# Thetis_RevF3_SCH.net
KiCad netlist of a schematic drawn in EAGLE
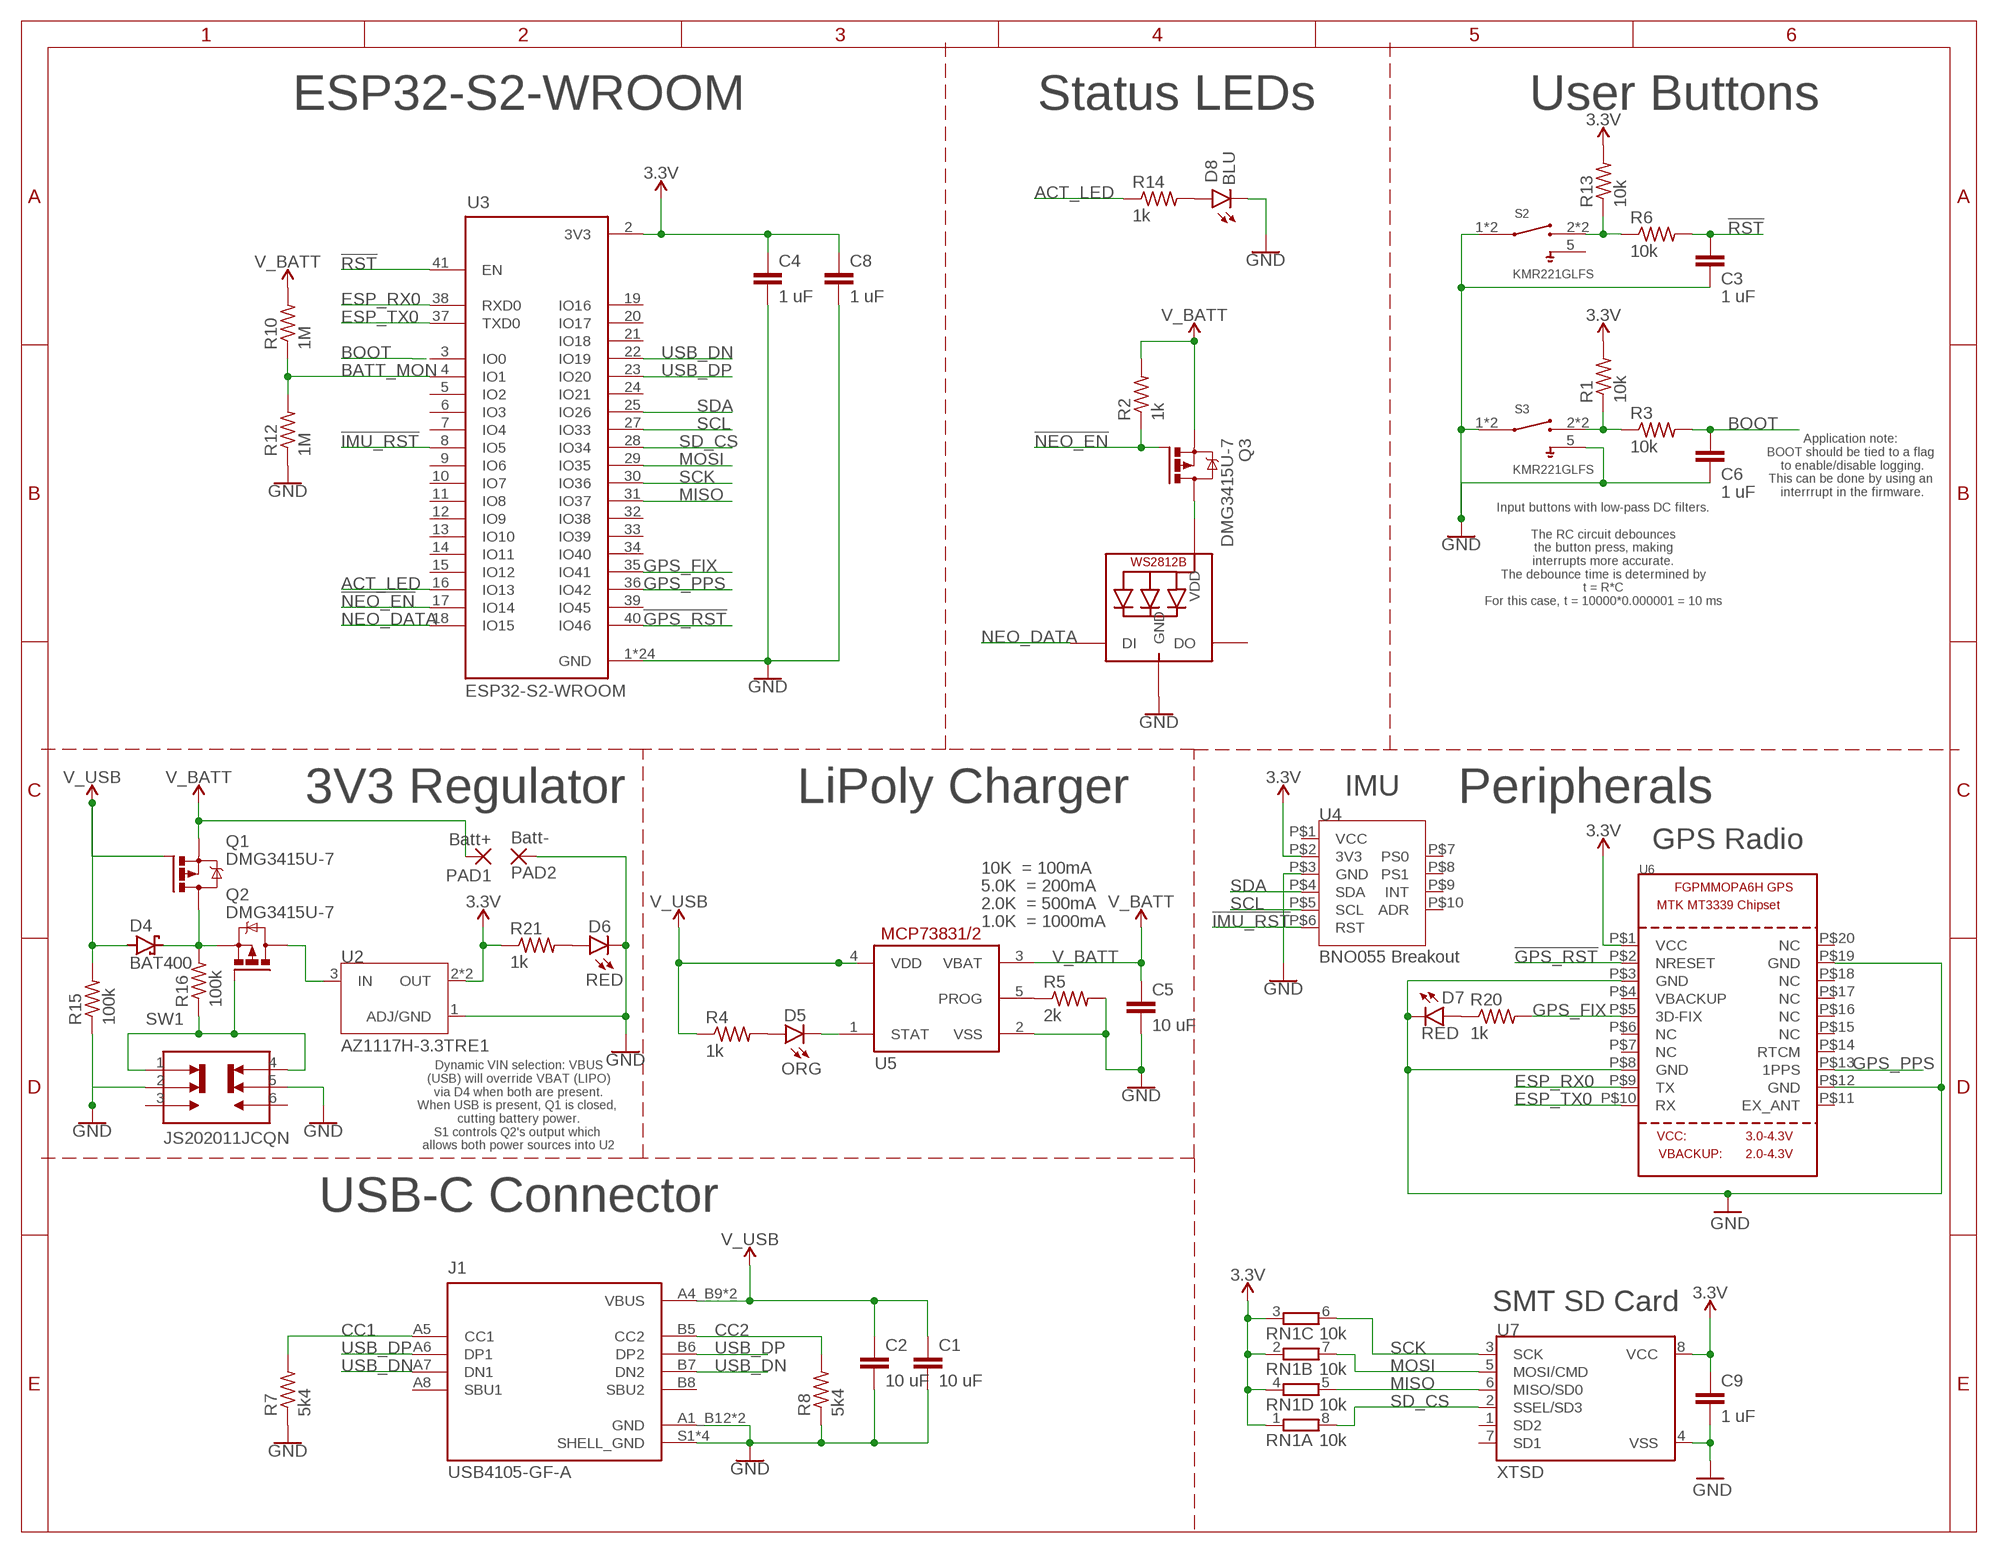
[diagram p0: schematic, sheet 1]

(export (version "E")
  (design (tool "Eeschema 10.0.6"))
  (components
    (comp (ref "C1")
      (value "10 uF")
      (footprint "eagle-import:C0603")
      (libsource (lib "eagle-import") (part "C-EUC0603"))
    )
    (comp (ref "C2")
      (value "10 uF")
      (footprint "eagle-import:C0603")
      (libsource (lib "eagle-import") (part "C-EUC0603"))
    )
    (comp (ref "C3")
      (value "1 uF")
      (footprint "eagle-import:C0603")
      (libsource (lib "eagle-import") (part "C-EUC0603"))
    )
    (comp (ref "C4")
      (value "1 uF")
      (footprint "eagle-import:C0603")
      (libsource (lib "eagle-import") (part "C-EUC0603"))
    )
    (comp (ref "C5")
      (value "10 uF")
      (footprint "eagle-import:C0603")
      (libsource (lib "eagle-import") (part "C-EUC0603"))
    )
    (comp (ref "C6")
      (value "1 uF")
      (footprint "eagle-import:C0603")
      (libsource (lib "eagle-import") (part "C-EUC0603"))
    )
    (comp (ref "C8")
      (value "1 uF")
      (footprint "eagle-import:C0603")
      (libsource (lib "eagle-import") (part "C-EUC0603"))
    )
    (comp (ref "C9")
      (value "1 uF")
      (footprint "eagle-import:C0603")
      (libsource (lib "eagle-import") (part "C-EUC0603"))
    )
    (comp (ref "D4")
      (value "BAT400")
      (footprint "eagle-import:SOT23")
      (libsource (lib "eagle-import") (part "BAS40"))
    )
    (comp (ref "D5")
      (value "ORG")
      (footprint "eagle-import:LEDC1608X65N")
      (libsource (lib "eagle-import") (part "CHIP-ROUND-G_0603"))
    )
    (comp (ref "D6")
      (value "RED")
      (footprint "eagle-import:LEDC1608X65N")
      (libsource (lib "eagle-import") (part "CHIP-ROUND-G_0603"))
    )
    (comp (ref "D7")
      (value "RED")
      (footprint "eagle-import:LEDC1608X35N")
      (libsource (lib "eagle-import") (part "CHIP-FLAT-Y_0603-0.35MM"))
    )
    (comp (ref "D8")
      (value "BLU")
      (footprint "eagle-import:LEDC1608X65N")
      (libsource (lib "eagle-import") (part "CHIP-ROUND-G_0603"))
    )
    (comp (ref "J1")
      (value "USB4105-GF-A")
      (footprint "eagle-import:GCT_USB4105-GF-A")
      (fields (field (name "MF") "GCT"))
      (libsource (lib "eagle-import") (part "USB4105-GF-A"))
    )
    (comp (ref "LED1")
      (value "WS2812B3535")
      (footprint "eagle-import:LED3535")
      (libsource (lib "eagle-import") (part "WS2812B3535"))
    )
    (comp (ref "PAD1")
      (value "Batt+")
      (footprint "eagle-import:SMD2,54-5,08")
      (libsource (lib "eagle-import") (part "SMD5"))
    )
    (comp (ref "PAD2")
      (value "Batt-")
      (footprint "eagle-import:SMD2,54-5,08")
      (libsource (lib "eagle-import") (part "SMD5"))
    )
    (comp (ref "Q1")
      (value "DMG3415U-7")
      (footprint "eagle-import:SOT23")
      (fields (field (name "MANUFACTURER") "ON Semiconductor") (field (name "MPN") "BSS84"))
      (libsource (lib "eagle-import") (part "PMOSFET_BSS84"))
    )
    (comp (ref "Q2")
      (value "DMG3415U-7")
      (footprint "eagle-import:SOT23")
      (fields (field (name "MANUFACTURER") "ON Semiconductor") (field (name "MPN") "BSS84"))
      (libsource (lib "eagle-import") (part "PMOSFET_BSS84"))
    )
    (comp (ref "Q3")
      (value "DMG3415U-7")
      (footprint "eagle-import:SOT23")
      (fields (field (name "MANUFACTURER") "ON Semiconductor") (field (name "MPN") "BSS84"))
      (libsource (lib "eagle-import") (part "PMOSFET_BSS84"))
    )
    (comp (ref "R1")
      (value "10k")
      (footprint "eagle-import:R0603")
      (libsource (lib "eagle-import") (part "R-US_R0603"))
    )
    (comp (ref "R2")
      (value "1k")
      (footprint "eagle-import:R0603")
      (libsource (lib "eagle-import") (part "R-US_R0603"))
    )
    (comp (ref "R3")
      (value "10k")
      (footprint "eagle-import:R0603")
      (libsource (lib "eagle-import") (part "R-US_R0603"))
    )
    (comp (ref "R4")
      (value "1k")
      (footprint "eagle-import:R0603")
      (libsource (lib "eagle-import") (part "R-US_R0603"))
    )
    (comp (ref "R5")
      (value "2k")
      (footprint "eagle-import:R0603")
      (libsource (lib "eagle-import") (part "R-US_R0603"))
    )
    (comp (ref "R6")
      (value "10k")
      (footprint "eagle-import:R0603")
      (libsource (lib "eagle-import") (part "R-US_R0603"))
    )
    (comp (ref "R7")
      (value "5k4")
      (footprint "eagle-import:R0603")
      (libsource (lib "eagle-import") (part "R-US_R0603"))
    )
    (comp (ref "R8")
      (value "5k4")
      (footprint "eagle-import:R0603")
      (libsource (lib "eagle-import") (part "R-US_R0603"))
    )
    (comp (ref "R10")
      (value "1M")
      (footprint "eagle-import:R0603")
      (libsource (lib "eagle-import") (part "R-US_R0603"))
    )
    (comp (ref "R12")
      (value "1M")
      (footprint "eagle-import:R0603")
      (libsource (lib "eagle-import") (part "R-US_R0603"))
    )
    (comp (ref "R13")
      (value "10k")
      (footprint "eagle-import:R0603")
      (libsource (lib "eagle-import") (part "R-US_R0603"))
    )
    (comp (ref "R14")
      (value "1k")
      (footprint "eagle-import:R0603")
      (libsource (lib "eagle-import") (part "R-US_R0603"))
    )
    (comp (ref "R15")
      (value "100k")
      (footprint "eagle-import:R0603")
      (libsource (lib "eagle-import") (part "R-US_R0603"))
    )
    (comp (ref "R16")
      (value "100k")
      (footprint "eagle-import:R0603")
      (libsource (lib "eagle-import") (part "R-US_R0603"))
    )
    (comp (ref "R20")
      (value "1k")
      (footprint "eagle-import:R0603")
      (libsource (lib "eagle-import") (part "R-US_R0603"))
    )
    (comp (ref "R21")
      (value "1k")
      (footprint "eagle-import:R0603")
      (libsource (lib "eagle-import") (part "R-US_R0603"))
    )
    (comp (ref "RN1")
      (value "10k")
      (footprint "eagle-import:EXBN8V")
      (libsource (lib "eagle-import") (part "4R-NEXBN8V"))
    )
    (comp (ref "S2")
      (value "KMR221GLFS")
      (footprint "eagle-import:SW_KMR221GLFS")
      (fields (field (name "MANUFACTURER") "CnK"))
      (libsource (lib "eagle-import") (part "KMR221GLFS"))
    )
    (comp (ref "S3")
      (value "KMR221GLFS")
      (footprint "eagle-import:SW_KMR221GLFS")
      (fields (field (name "MANUFACTURER") "CnK"))
      (libsource (lib "eagle-import") (part "KMR221GLFS"))
    )
    (comp (ref "SW1")
      (value "JS202011JCQN")
      (footprint "eagle-import:SW_JS202011JCQN")
      (libsource (lib "eagle-import") (part "JS202011JCQN"))
    )
    (comp (ref "U2")
      (value "AZ1117H-3.3TRE1")
      (footprint "eagle-import:SOT230P700X180-4N")
      (fields (field (name "MF") "Diodes Inc.") (field (name "MP") "AZ1117EH-5.0TRG1"))
      (libsource (lib "eagle-import") (part "AZ1117EH-5.0TRG1"))
    )
    (comp (ref "U3")
      (value "ESP32-S2-WROOM")
      (footprint "eagle-import:XCVR_ESP32-S2-WROOM")
      (fields (field (name "MANUFACTURER") "Espressif Systems"))
      (libsource (lib "eagle-import") (part "ESP32-S2-WROOM"))
    )
    (comp (ref "U4")
      (value "BNO055 Breakout")
      (footprint "eagle-import:ADAFRUIT-BNO055-BREAKOUT-SMD")
      (libsource (lib "eagle-import") (part "ADAFRUIT-BNO055-BREAKOUT-SMD"))
    )
    (comp (ref "U5")
      (value "MCP73831/OT")
      (footprint "eagle-import:SOT23-5L")
      (libsource (lib "eagle-import") (part "MCP73831/OT"))
    )
    (comp (ref "U6")
      (value "GPS_FGPMMOPA6H")
      (footprint "eagle-import:FGPMMOPA6H")
      (libsource (lib "eagle-import") (part "GPS_FGPMMOPA6H"))
    )
    (comp (ref "U7")
      (value "XTSD")
      (footprint "eagle-import:LGA8_8X6")
      (libsource (lib "eagle-import") (part "SMT_SDCARD_8PIN"))
    )
  )
  (nets
    (net (code "1") (name "/ACT_LED") (class "Default")
      (node (ref "R14") (pin "1") (pinfunction "1_1") (pintype "passive"))
      (node (ref "U3") (pin "16") (pinfunction "IO13_16") (pintype "bidirectional"))
    )
    (net (code "2") (name "/BATT_MON") (class "Default")
      (node (ref "R10") (pin "1") (pinfunction "1_1") (pintype "passive"))
      (node (ref "R12") (pin "2") (pinfunction "2_2") (pintype "passive"))
      (node (ref "U3") (pin "4") (pinfunction "IO1_4") (pintype "bidirectional"))
    )
    (net (code "3") (name "/BOOT") (class "Default")
      (node (ref "C6") (pin "1") (pinfunction "1_1") (pintype "passive"))
      (node (ref "R3") (pin "2") (pinfunction "2_2") (pintype "passive"))
      (node (ref "U3") (pin "3") (pinfunction "IO0_3") (pintype "bidirectional"))
    )
    (net (code "4") (name "/CC1") (class "Default")
      (node (ref "J1") (pin "A5") (pinfunction "CC1_A5") (pintype "bidirectional"))
      (node (ref "R7") (pin "2") (pinfunction "2_2") (pintype "passive"))
    )
    (net (code "5") (name "/CC2") (class "Default")
      (node (ref "J1") (pin "B5") (pinfunction "CC2_B5") (pintype "bidirectional"))
      (node (ref "R8") (pin "2") (pinfunction "2_2") (pintype "passive"))
    )
    (net (code "6") (name "/ESP_RX0") (class "Default")
      (node (ref "U3") (pin "38") (pinfunction "RXD0_38") (pintype "bidirectional"))
      (node (ref "U6") (pin "P$9") (pinfunction "TX_P$9") (pintype "bidirectional"))
    )
    (net (code "7") (name "/ESP_TX0") (class "Default")
      (node (ref "U3") (pin "37") (pinfunction "TXD0_37") (pintype "bidirectional"))
      (node (ref "U6") (pin "P$10") (pinfunction "RX_P$10") (pintype "bidirectional"))
    )
    (net (code "8") (name "/GPS_FIX") (class "Default")
      (node (ref "R20") (pin "2") (pinfunction "2_2") (pintype "passive"))
      (node (ref "U3") (pin "35") (pinfunction "IO41_35") (pintype "bidirectional"))
      (node (ref "U6") (pin "P$5") (pinfunction "3D-FIX_P$5") (pintype "bidirectional"))
    )
    (net (code "9") (name "/GPS_PPS") (class "Default")
      (node (ref "U3") (pin "36") (pinfunction "IO42_36") (pintype "bidirectional"))
      (node (ref "U6") (pin "P$13") (pinfunction "1PPS_P$13") (pintype "bidirectional"))
    )
    (net (code "10") (name "/MISO") (class "Default")
      (node (ref "RN1") (pin "5") (pinfunction "2_5") (pintype "passive"))
      (node (ref "U3") (pin "31") (pinfunction "IO37_31") (pintype "bidirectional"))
      (node (ref "U7") (pin "6") (pinfunction "MISO/SD0_6") (pintype "bidirectional"))
    )
    (net (code "11") (name "/MOSI") (class "Default")
      (node (ref "RN1") (pin "7") (pinfunction "2_7") (pintype "passive"))
      (node (ref "U3") (pin "29") (pinfunction "IO35_29") (pintype "bidirectional"))
      (node (ref "U7") (pin "5") (pinfunction "MOSI/CMD_5") (pintype "bidirectional"))
    )
    (net (code "12") (name "/NEO_DATA") (class "Default")
      (node (ref "LED1") (pin "1") (pinfunction "DI_1") (pintype "input"))
      (node (ref "U3") (pin "18") (pinfunction "IO15_18") (pintype "bidirectional"))
    )
    (net (code "13") (name "/SCK") (class "Default")
      (node (ref "RN1") (pin "6") (pinfunction "2_6") (pintype "passive"))
      (node (ref "U3") (pin "30") (pinfunction "IO36_30") (pintype "bidirectional"))
      (node (ref "U7") (pin "3") (pinfunction "SCK_3") (pintype "input"))
    )
    (net (code "14") (name "/SCL") (class "Default")
      (node (ref "U3") (pin "27") (pinfunction "IO33_27") (pintype "bidirectional"))
      (node (ref "U4") (pin "P$5") (pinfunction "SCL_P$5") (pintype "bidirectional"))
    )
    (net (code "15") (name "/SDA") (class "Default")
      (node (ref "U3") (pin "25") (pinfunction "IO26_25") (pintype "bidirectional"))
      (node (ref "U4") (pin "P$4") (pinfunction "SDA_P$4") (pintype "bidirectional"))
    )
    (net (code "16") (name "/SD_CS") (class "Default")
      (node (ref "RN1") (pin "8") (pinfunction "2_8") (pintype "passive"))
      (node (ref "U3") (pin "28") (pinfunction "IO34_28") (pintype "bidirectional"))
      (node (ref "U7") (pin "2") (pinfunction "SSEL/SD3_2") (pintype "bidirectional"))
    )
    (net (code "17") (name "/USB_DN") (class "Default")
      (node (ref "J1") (pin "A7") (pinfunction "DN1_A7") (pintype "bidirectional"))
      (node (ref "J1") (pin "B7") (pinfunction "DN2_B7") (pintype "bidirectional"))
      (node (ref "U3") (pin "22") (pinfunction "IO19_22") (pintype "bidirectional"))
    )
    (net (code "18") (name "/USB_DP") (class "Default")
      (node (ref "J1") (pin "A6") (pinfunction "DP1_A6") (pintype "bidirectional"))
      (node (ref "J1") (pin "B6") (pinfunction "DP2_B6") (pintype "bidirectional"))
      (node (ref "U3") (pin "23") (pinfunction "IO20_23") (pintype "bidirectional"))
    )
    (net (code "19") (name "/VCC") (class "Default")
      (node (ref "U4") (pin "P$1") (pinfunction "VCC_P$1") (pintype "power_in"))
    )
    (net (code "20") (name "/~{GPS_RST}") (class "Default")
      (node (ref "U3") (pin "40") (pinfunction "IO46_40") (pintype "bidirectional"))
      (node (ref "U6") (pin "P$2") (pinfunction "NRESET_P$2") (pintype "bidirectional"))
    )
    (net (code "21") (name "/~{IMU_RST}") (class "Default")
      (node (ref "U3") (pin "8") (pinfunction "IO5_8") (pintype "bidirectional"))
      (node (ref "U4") (pin "P$6") (pinfunction "RST_P$6") (pintype "input"))
    )
    (net (code "22") (name "/~{NEO_EN}") (class "Default")
      (node (ref "Q3") (pin "1") (pinfunction "G_1") (pintype "passive"))
      (node (ref "R2") (pin "1") (pinfunction "1_1") (pintype "passive"))
      (node (ref "U3") (pin "17") (pinfunction "IO14_17") (pintype "bidirectional"))
    )
    (net (code "23") (name "/~{RST}") (class "Default")
      (node (ref "C3") (pin "1") (pinfunction "1_1") (pintype "passive"))
      (node (ref "R6") (pin "2") (pinfunction "2_2") (pintype "passive"))
      (node (ref "U3") (pin "41") (pinfunction "EN_41") (pintype "input"))
    )
    (net (code "24") (name "3.3V") (class "Default")
      (node (ref "C4") (pin "1") (pinfunction "1_1") (pintype "passive"))
      (node (ref "C8") (pin "1") (pinfunction "1_1") (pintype "passive"))
      (node (ref "C9") (pin "1") (pinfunction "1_1") (pintype "passive"))
      (node (ref "R1") (pin "2") (pinfunction "2_2") (pintype "passive"))
      (node (ref "R13") (pin "2") (pinfunction "2_2") (pintype "passive"))
      (node (ref "R21") (pin "1") (pinfunction "1_1") (pintype "passive"))
      (node (ref "RN1") (pin "1") (pinfunction "1_1") (pintype "passive"))
      (node (ref "RN1") (pin "2") (pinfunction "1_2") (pintype "passive"))
      (node (ref "RN1") (pin "3") (pinfunction "1_3") (pintype "passive"))
      (node (ref "RN1") (pin "4") (pinfunction "1_4") (pintype "passive"))
      (node (ref "U2") (pin "2") (pinfunction "OUT_2") (pintype "output"))
      (node (ref "U2") (pin "4") (pinfunction "OUT_4") (pintype "output"))
      (node (ref "U3") (pin "2") (pinfunction "3V3_2") (pintype "power_in"))
      (node (ref "U4") (pin "P$2") (pinfunction "3V3_P$2") (pintype "power_in"))
      (node (ref "U6") (pin "P$1") (pinfunction "VCC_P$1") (pintype "bidirectional"))
      (node (ref "U7") (pin "8") (pinfunction "VCC_8") (pintype "power_in"))
    )
    (net (code "25") (name "GND") (class "Default")
      (node (ref "C1") (pin "2") (pinfunction "2_2") (pintype "passive"))
      (node (ref "C2") (pin "2") (pinfunction "2_2") (pintype "passive"))
      (node (ref "C3") (pin "2") (pinfunction "2_2") (pintype "passive"))
      (node (ref "C4") (pin "2") (pinfunction "2_2") (pintype "passive"))
      (node (ref "C5") (pin "2") (pinfunction "2_2") (pintype "passive"))
      (node (ref "C6") (pin "2") (pinfunction "2_2") (pintype "passive"))
      (node (ref "C8") (pin "2") (pinfunction "2_2") (pintype "passive"))
      (node (ref "C9") (pin "2") (pinfunction "2_2") (pintype "passive"))
      (node (ref "D6") (pin "C") (pinfunction "C_C") (pintype "passive"))
      (node (ref "D7") (pin "C") (pinfunction "C_C") (pintype "passive"))
      (node (ref "D8") (pin "C") (pinfunction "C_C") (pintype "passive"))
      (node (ref "J1") (pin "A1_B12") (pinfunction "GND_A1_B12") (pintype "power_in"))
      (node (ref "J1") (pin "B1_A12") (pinfunction "GND_B1_A12") (pintype "power_in"))
      (node (ref "J1") (pin "S1") (pinfunction "SHELL_GND_S1") (pintype "power_in"))
      (node (ref "J1") (pin "S2") (pinfunction "SHELL_GND_S2") (pintype "power_in"))
      (node (ref "J1") (pin "S3") (pinfunction "SHELL_GND_S3") (pintype "power_in"))
      (node (ref "J1") (pin "S4") (pinfunction "SHELL_GND_S4") (pintype "power_in"))
      (node (ref "LED1") (pin "4") (pinfunction "GND_4") (pintype "power_in"))
      (node (ref "PAD2") (pin "1") (pinfunction "P_1") (pintype "passive"))
      (node (ref "R12") (pin "1") (pinfunction "1_1") (pintype "passive"))
      (node (ref "R15") (pin "1") (pinfunction "1_1") (pintype "passive"))
      (node (ref "R5") (pin "2") (pinfunction "2_2") (pintype "passive"))
      (node (ref "R7") (pin "1") (pinfunction "1_1") (pintype "passive"))
      (node (ref "R8") (pin "1") (pinfunction "1_1") (pintype "passive"))
      (node (ref "S2") (pin "1") (pinfunction "1_1") (pintype "passive"))
      (node (ref "S2") (pin "4") (pinfunction "1_4") (pintype "passive"))
      (node (ref "S3") (pin "1") (pinfunction "1_1") (pintype "passive"))
      (node (ref "S3") (pin "4") (pinfunction "1_4") (pintype "passive"))
      (node (ref "S3") (pin "5") (pinfunction "5_5") (pintype "passive"))
      (node (ref "SW1") (pin "2") (pinfunction "2_2") (pintype "passive"))
      (node (ref "SW1") (pin "5") (pinfunction "6_5") (pintype "passive"))
      (node (ref "U2") (pin "1") (pinfunction "ADJ/GND_1") (pintype "power_in"))
      (node (ref "U3") (pin "1") (pinfunction "GND_1") (pintype "power_in"))
      (node (ref "U3") (pin "26") (pinfunction "GND_26") (pintype "power_in"))
      (node (ref "U3") (pin "42") (pinfunction "GND_42") (pintype "power_in"))
      (node (ref "U3") (pin "43.1") (pinfunction "GND_43.1") (pintype "power_in"))
      (node (ref "U3") (pin "43.10") (pinfunction "GND_43.10") (pintype "power_in"))
      (node (ref "U3") (pin "43.11") (pinfunction "GND_43.11") (pintype "power_in"))
      (node (ref "U3") (pin "43.12") (pinfunction "GND_43.12") (pintype "power_in"))
      (node (ref "U3") (pin "43.13") (pinfunction "GND_43.13") (pintype "power_in"))
      (node (ref "U3") (pin "43.14") (pinfunction "GND_43.14") (pintype "power_in"))
      (node (ref "U3") (pin "43.15") (pinfunction "GND_43.15") (pintype "power_in"))
      (node (ref "U3") (pin "43.16") (pinfunction "GND_43.16") (pintype "power_in"))
      (node (ref "U3") (pin "43.17") (pinfunction "GND_43.17") (pintype "power_in"))
      (node (ref "U3") (pin "43.18") (pinfunction "GND_43.18") (pintype "power_in"))
      (node (ref "U3") (pin "43.19") (pinfunction "GND_43.19") (pintype "power_in"))
      (node (ref "U3") (pin "43.2") (pinfunction "GND_43.2") (pintype "power_in"))
      (node (ref "U3") (pin "43.20") (pinfunction "GND_43.20") (pintype "power_in"))
      (node (ref "U3") (pin "43.21") (pinfunction "GND_43.21") (pintype "power_in"))
      (node (ref "U3") (pin "43.3") (pinfunction "GND_43.3") (pintype "power_in"))
      (node (ref "U3") (pin "43.4") (pinfunction "GND_43.4") (pintype "power_in"))
      (node (ref "U3") (pin "43.5") (pinfunction "GND_43.5") (pintype "power_in"))
      (node (ref "U3") (pin "43.6") (pinfunction "GND_43.6") (pintype "power_in"))
      (node (ref "U3") (pin "43.7") (pinfunction "GND_43.7") (pintype "power_in"))
      (node (ref "U3") (pin "43.8") (pinfunction "GND_43.8") (pintype "power_in"))
      (node (ref "U3") (pin "43.9") (pinfunction "GND_43.9") (pintype "power_in"))
      (node (ref "U4") (pin "P$3") (pinfunction "GND_P$3") (pintype "power_in"))
      (node (ref "U5") (pin "2") (pinfunction "VSS_2") (pintype "power_in"))
      (node (ref "U6") (pin "P$12") (pinfunction "GND_P$12") (pintype "bidirectional"))
      (node (ref "U6") (pin "P$19") (pinfunction "GND_P$19") (pintype "bidirectional"))
      (node (ref "U6") (pin "P$3") (pinfunction "GND_P$3") (pintype "bidirectional"))
      (node (ref "U6") (pin "P$8") (pinfunction "GND_P$8") (pintype "bidirectional"))
      (node (ref "U7") (pin "4") (pinfunction "VSS_4") (pintype "power_in"))
    )
    (net (code "26") (name "Net-(D4-C)") (class "Default")
      (node (ref "D4") (pin "3") (pinfunction "C_3") (pintype "passive"))
      (node (ref "Q1") (pin "3") (pinfunction "D_3") (pintype "passive"))
      (node (ref "Q2") (pin "2") (pinfunction "S_2") (pintype "passive"))
      (node (ref "R16") (pin "2") (pinfunction "2_2") (pintype "passive"))
    )
    (net (code "27") (name "Net-(D5-PadA)") (class "Default")
      (node (ref "D5") (pin "A") (pinfunction "A_A") (pintype "passive"))
      (node (ref "R4") (pin "2") (pinfunction "2_2") (pintype "passive"))
    )
    (net (code "28") (name "Net-(D6-PadA)") (class "Default")
      (node (ref "D6") (pin "A") (pinfunction "A_A") (pintype "passive"))
      (node (ref "R21") (pin "2") (pinfunction "2_2") (pintype "passive"))
    )
    (net (code "29") (name "Net-(D7-PadA)") (class "Default")
      (node (ref "D7") (pin "A") (pinfunction "A_A") (pintype "passive"))
      (node (ref "R20") (pin "1") (pinfunction "1_1") (pintype "passive"))
    )
    (net (code "30") (name "Net-(D8-PadA)") (class "Default")
      (node (ref "D8") (pin "A") (pinfunction "A_A") (pintype "passive"))
      (node (ref "R14") (pin "2") (pinfunction "2_2") (pintype "passive"))
    )
    (net (code "31") (name "Net-(LED1-VDD)") (class "Default")
      (node (ref "LED1") (pin "2") (pinfunction "VDD_2") (pintype "power_in"))
      (node (ref "Q3") (pin "3") (pinfunction "D_3") (pintype "passive"))
    )
    (net (code "32") (name "Net-(Q2-D)") (class "Default")
      (node (ref "Q2") (pin "3") (pinfunction "D_3") (pintype "passive"))
      (node (ref "U2") (pin "3") (pinfunction "IN_3") (pintype "input"))
    )
    (net (code "33") (name "Net-(Q2-G)") (class "Default")
      (node (ref "Q2") (pin "1") (pinfunction "G_1") (pintype "passive"))
      (node (ref "R16") (pin "1") (pinfunction "1_1") (pintype "passive"))
      (node (ref "SW1") (pin "1") (pinfunction "1_1") (pintype "passive"))
      (node (ref "SW1") (pin "4") (pinfunction "5_4") (pintype "passive"))
    )
    (net (code "34") (name "Net-(R1-Pad1)") (class "Default")
      (node (ref "R1") (pin "1") (pinfunction "1_1") (pintype "passive"))
      (node (ref "R3") (pin "1") (pinfunction "1_1") (pintype "passive"))
      (node (ref "S3") (pin "2") (pinfunction "3_2") (pintype "passive"))
      (node (ref "S3") (pin "3") (pinfunction "3_3") (pintype "passive"))
    )
    (net (code "35") (name "Net-(R13-Pad1)") (class "Default")
      (node (ref "R13") (pin "1") (pinfunction "1_1") (pintype "passive"))
      (node (ref "R6") (pin "1") (pinfunction "1_1") (pintype "passive"))
      (node (ref "S2") (pin "2") (pinfunction "3_2") (pintype "passive"))
      (node (ref "S2") (pin "3") (pinfunction "3_3") (pintype "passive"))
    )
    (net (code "36") (name "Net-(U5-PROG)") (class "Default")
      (node (ref "R5") (pin "1") (pinfunction "1_1") (pintype "passive"))
      (node (ref "U5") (pin "5") (pinfunction "PROG_5") (pintype "input"))
    )
    (net (code "37") (name "Net-(U5-STAT)") (class "Default")
      (node (ref "D5") (pin "C") (pinfunction "C_C") (pintype "passive"))
      (node (ref "U5") (pin "1") (pinfunction "STAT_1") (pintype "output"))
    )
    (net (code "38") (name "V_BATT") (class "Default")
      (node (ref "C5") (pin "1") (pinfunction "1_1") (pintype "passive"))
      (node (ref "PAD1") (pin "1") (pinfunction "P_1") (pintype "passive"))
      (node (ref "Q1") (pin "2") (pinfunction "S_2") (pintype "passive"))
      (node (ref "Q3") (pin "2") (pinfunction "S_2") (pintype "passive"))
      (node (ref "R10") (pin "2") (pinfunction "2_2") (pintype "passive"))
      (node (ref "R2") (pin "2") (pinfunction "2_2") (pintype "passive"))
      (node (ref "U5") (pin "3") (pinfunction "VBAT_3") (pintype "bidirectional"))
    )
    (net (code "39") (name "V_USB") (class "Default")
      (node (ref "C1") (pin "1") (pinfunction "1_1") (pintype "passive"))
      (node (ref "C2") (pin "1") (pinfunction "1_1") (pintype "passive"))
      (node (ref "D4") (pin "1") (pinfunction "A_1") (pintype "passive"))
      (node (ref "J1") (pin "A4_B9") (pinfunction "VBUS_A4_B9") (pintype "power_in"))
      (node (ref "J1") (pin "B4_A9") (pinfunction "VBUS_B4_A9") (pintype "power_in"))
      (node (ref "Q1") (pin "1") (pinfunction "G_1") (pintype "passive"))
      (node (ref "R15") (pin "2") (pinfunction "2_2") (pintype "passive"))
      (node (ref "R4") (pin "1") (pinfunction "1_1") (pintype "passive"))
      (node (ref "U5") (pin "4") (pinfunction "VDD_4") (pintype "power_in"))
    )
    (net (code "40") (name "unconnected-(J1-SBU1-PadA8)") (class "Default")
      (node (ref "J1") (pin "A8") (pinfunction "SBU1_A8") (pintype "bidirectional"))
    )
    (net (code "41") (name "unconnected-(J1-SBU2-PadB8)") (class "Default")
      (node (ref "J1") (pin "B8") (pinfunction "SBU2_B8") (pintype "bidirectional"))
    )
    (net (code "42") (name "unconnected-(LED1-DO-Pad3)") (class "Default")
      (node (ref "LED1") (pin "3") (pinfunction "DO_3") (pintype "output"))
    )
    (net (code "43") (name "unconnected-(S2-Pad5)") (class "Default")
      (node (ref "S2") (pin "5") (pinfunction "5_5") (pintype "passive"))
    )
    (net (code "44") (name "unconnected-(SW1-7-Pad6)") (class "Default")
      (node (ref "SW1") (pin "6") (pinfunction "7_6") (pintype "passive"))
    )
    (net (code "45") (name "unconnected-(SW1-Pad3)") (class "Default")
      (node (ref "SW1") (pin "3") (pinfunction "3_3") (pintype "passive"))
    )
    (net (code "46") (name "unconnected-(U3-IO2-Pad5)") (class "Default")
      (node (ref "U3") (pin "5") (pinfunction "IO2_5") (pintype "bidirectional"))
    )
    (net (code "47") (name "unconnected-(U3-IO3-Pad6)") (class "Default")
      (node (ref "U3") (pin "6") (pinfunction "IO3_6") (pintype "bidirectional"))
    )
    (net (code "48") (name "unconnected-(U3-IO4-Pad7)") (class "Default")
      (node (ref "U3") (pin "7") (pinfunction "IO4_7") (pintype "bidirectional"))
    )
    (net (code "49") (name "unconnected-(U3-IO6-Pad9)") (class "Default")
      (node (ref "U3") (pin "9") (pinfunction "IO6_9") (pintype "bidirectional"))
    )
    (net (code "50") (name "unconnected-(U3-IO7-Pad10)") (class "Default")
      (node (ref "U3") (pin "10") (pinfunction "IO7_10") (pintype "bidirectional"))
    )
    (net (code "51") (name "unconnected-(U3-IO8-Pad11)") (class "Default")
      (node (ref "U3") (pin "11") (pinfunction "IO8_11") (pintype "bidirectional"))
    )
    (net (code "52") (name "unconnected-(U3-IO9-Pad12)") (class "Default")
      (node (ref "U3") (pin "12") (pinfunction "IO9_12") (pintype "bidirectional"))
    )
    (net (code "53") (name "unconnected-(U3-IO10-Pad13)") (class "Default")
      (node (ref "U3") (pin "13") (pinfunction "IO10_13") (pintype "bidirectional"))
    )
    (net (code "54") (name "unconnected-(U3-IO11-Pad14)") (class "Default")
      (node (ref "U3") (pin "14") (pinfunction "IO11_14") (pintype "bidirectional"))
    )
    (net (code "55") (name "unconnected-(U3-IO12-Pad15)") (class "Default")
      (node (ref "U3") (pin "15") (pinfunction "IO12_15") (pintype "bidirectional"))
    )
    (net (code "56") (name "unconnected-(U3-IO16-Pad19)") (class "Default")
      (node (ref "U3") (pin "19") (pinfunction "IO16_19") (pintype "bidirectional"))
    )
    (net (code "57") (name "unconnected-(U3-IO17-Pad20)") (class "Default")
      (node (ref "U3") (pin "20") (pinfunction "IO17_20") (pintype "bidirectional"))
    )
    (net (code "58") (name "unconnected-(U3-IO18-Pad21)") (class "Default")
      (node (ref "U3") (pin "21") (pinfunction "IO18_21") (pintype "bidirectional"))
    )
    (net (code "59") (name "unconnected-(U3-IO21-Pad24)") (class "Default")
      (node (ref "U3") (pin "24") (pinfunction "IO21_24") (pintype "bidirectional"))
    )
    (net (code "60") (name "unconnected-(U3-IO38-Pad32)") (class "Default")
      (node (ref "U3") (pin "32") (pinfunction "IO38_32") (pintype "bidirectional"))
    )
    (net (code "61") (name "unconnected-(U3-IO39-Pad33)") (class "Default")
      (node (ref "U3") (pin "33") (pinfunction "IO39_33") (pintype "bidirectional"))
    )
    (net (code "62") (name "unconnected-(U3-IO40-Pad34)") (class "Default")
      (node (ref "U3") (pin "34") (pinfunction "IO40_34") (pintype "bidirectional"))
    )
    (net (code "63") (name "unconnected-(U3-IO45-Pad39)") (class "Default")
      (node (ref "U3") (pin "39") (pinfunction "IO45_39") (pintype "bidirectional"))
    )
    (net (code "64") (name "unconnected-(U4-ADR-PadP$10)") (class "Default")
      (node (ref "U4") (pin "P$10") (pinfunction "ADR_P$10") (pintype "bidirectional"))
    )
    (net (code "65") (name "unconnected-(U4-INT-PadP$9)") (class "Default")
      (node (ref "U4") (pin "P$9") (pinfunction "INT_P$9") (pintype "bidirectional"))
    )
    (net (code "66") (name "unconnected-(U4-PS0-PadP$7)") (class "Default")
      (node (ref "U4") (pin "P$7") (pinfunction "PS0_P$7") (pintype "bidirectional"))
    )
    (net (code "67") (name "unconnected-(U4-PS1-PadP$8)") (class "Default")
      (node (ref "U4") (pin "P$8") (pinfunction "PS1_P$8") (pintype "bidirectional"))
    )
    (net (code "68") (name "unconnected-(U6-EX_ANT-PadP$11)") (class "Default")
      (node (ref "U6") (pin "P$11") (pinfunction "EX_ANT_P$11") (pintype "bidirectional"))
    )
    (net (code "69") (name "unconnected-(U6-NC-PadP$6)") (class "Default")
      (node (ref "U6") (pin "P$6") (pinfunction "NC_P$6") (pintype "bidirectional"))
    )
    (net (code "70") (name "unconnected-(U6-NC-PadP$7)") (class "Default")
      (node (ref "U6") (pin "P$7") (pinfunction "NC_P$7") (pintype "bidirectional"))
    )
    (net (code "71") (name "unconnected-(U6-NC-PadP$15)") (class "Default")
      (node (ref "U6") (pin "P$15") (pinfunction "NC_P$15") (pintype "bidirectional"))
    )
    (net (code "72") (name "unconnected-(U6-NC-PadP$16)") (class "Default")
      (node (ref "U6") (pin "P$16") (pinfunction "NC_P$16") (pintype "bidirectional"))
    )
    (net (code "73") (name "unconnected-(U6-NC-PadP$17)") (class "Default")
      (node (ref "U6") (pin "P$17") (pinfunction "NC_P$17") (pintype "bidirectional"))
    )
    (net (code "74") (name "unconnected-(U6-NC-PadP$18)") (class "Default")
      (node (ref "U6") (pin "P$18") (pinfunction "NC_P$18") (pintype "bidirectional"))
    )
    (net (code "75") (name "unconnected-(U6-NC-PadP$20)") (class "Default")
      (node (ref "U6") (pin "P$20") (pinfunction "NC_P$20") (pintype "bidirectional"))
    )
    (net (code "76") (name "unconnected-(U6-RTCM-PadP$14)") (class "Default")
      (node (ref "U6") (pin "P$14") (pinfunction "RTCM_P$14") (pintype "bidirectional"))
    )
    (net (code "77") (name "unconnected-(U6-VBACKUP-PadP$4)") (class "Default")
      (node (ref "U6") (pin "P$4") (pinfunction "VBACKUP_P$4") (pintype "bidirectional"))
    )
    (net (code "78") (name "unconnected-(U7-SD1-Pad7)") (class "Default")
      (node (ref "U7") (pin "7") (pinfunction "SD1_7") (pintype "bidirectional"))
    )
    (net (code "79") (name "unconnected-(U7-SD2-Pad1)") (class "Default")
      (node (ref "U7") (pin "1") (pinfunction "SD2_1") (pintype "bidirectional"))
    )
  )
)
